# SCH_PCB-Hacker-Card-1_2024-07-07.net
KiCad netlist of a schematic drawn in EasyEDA
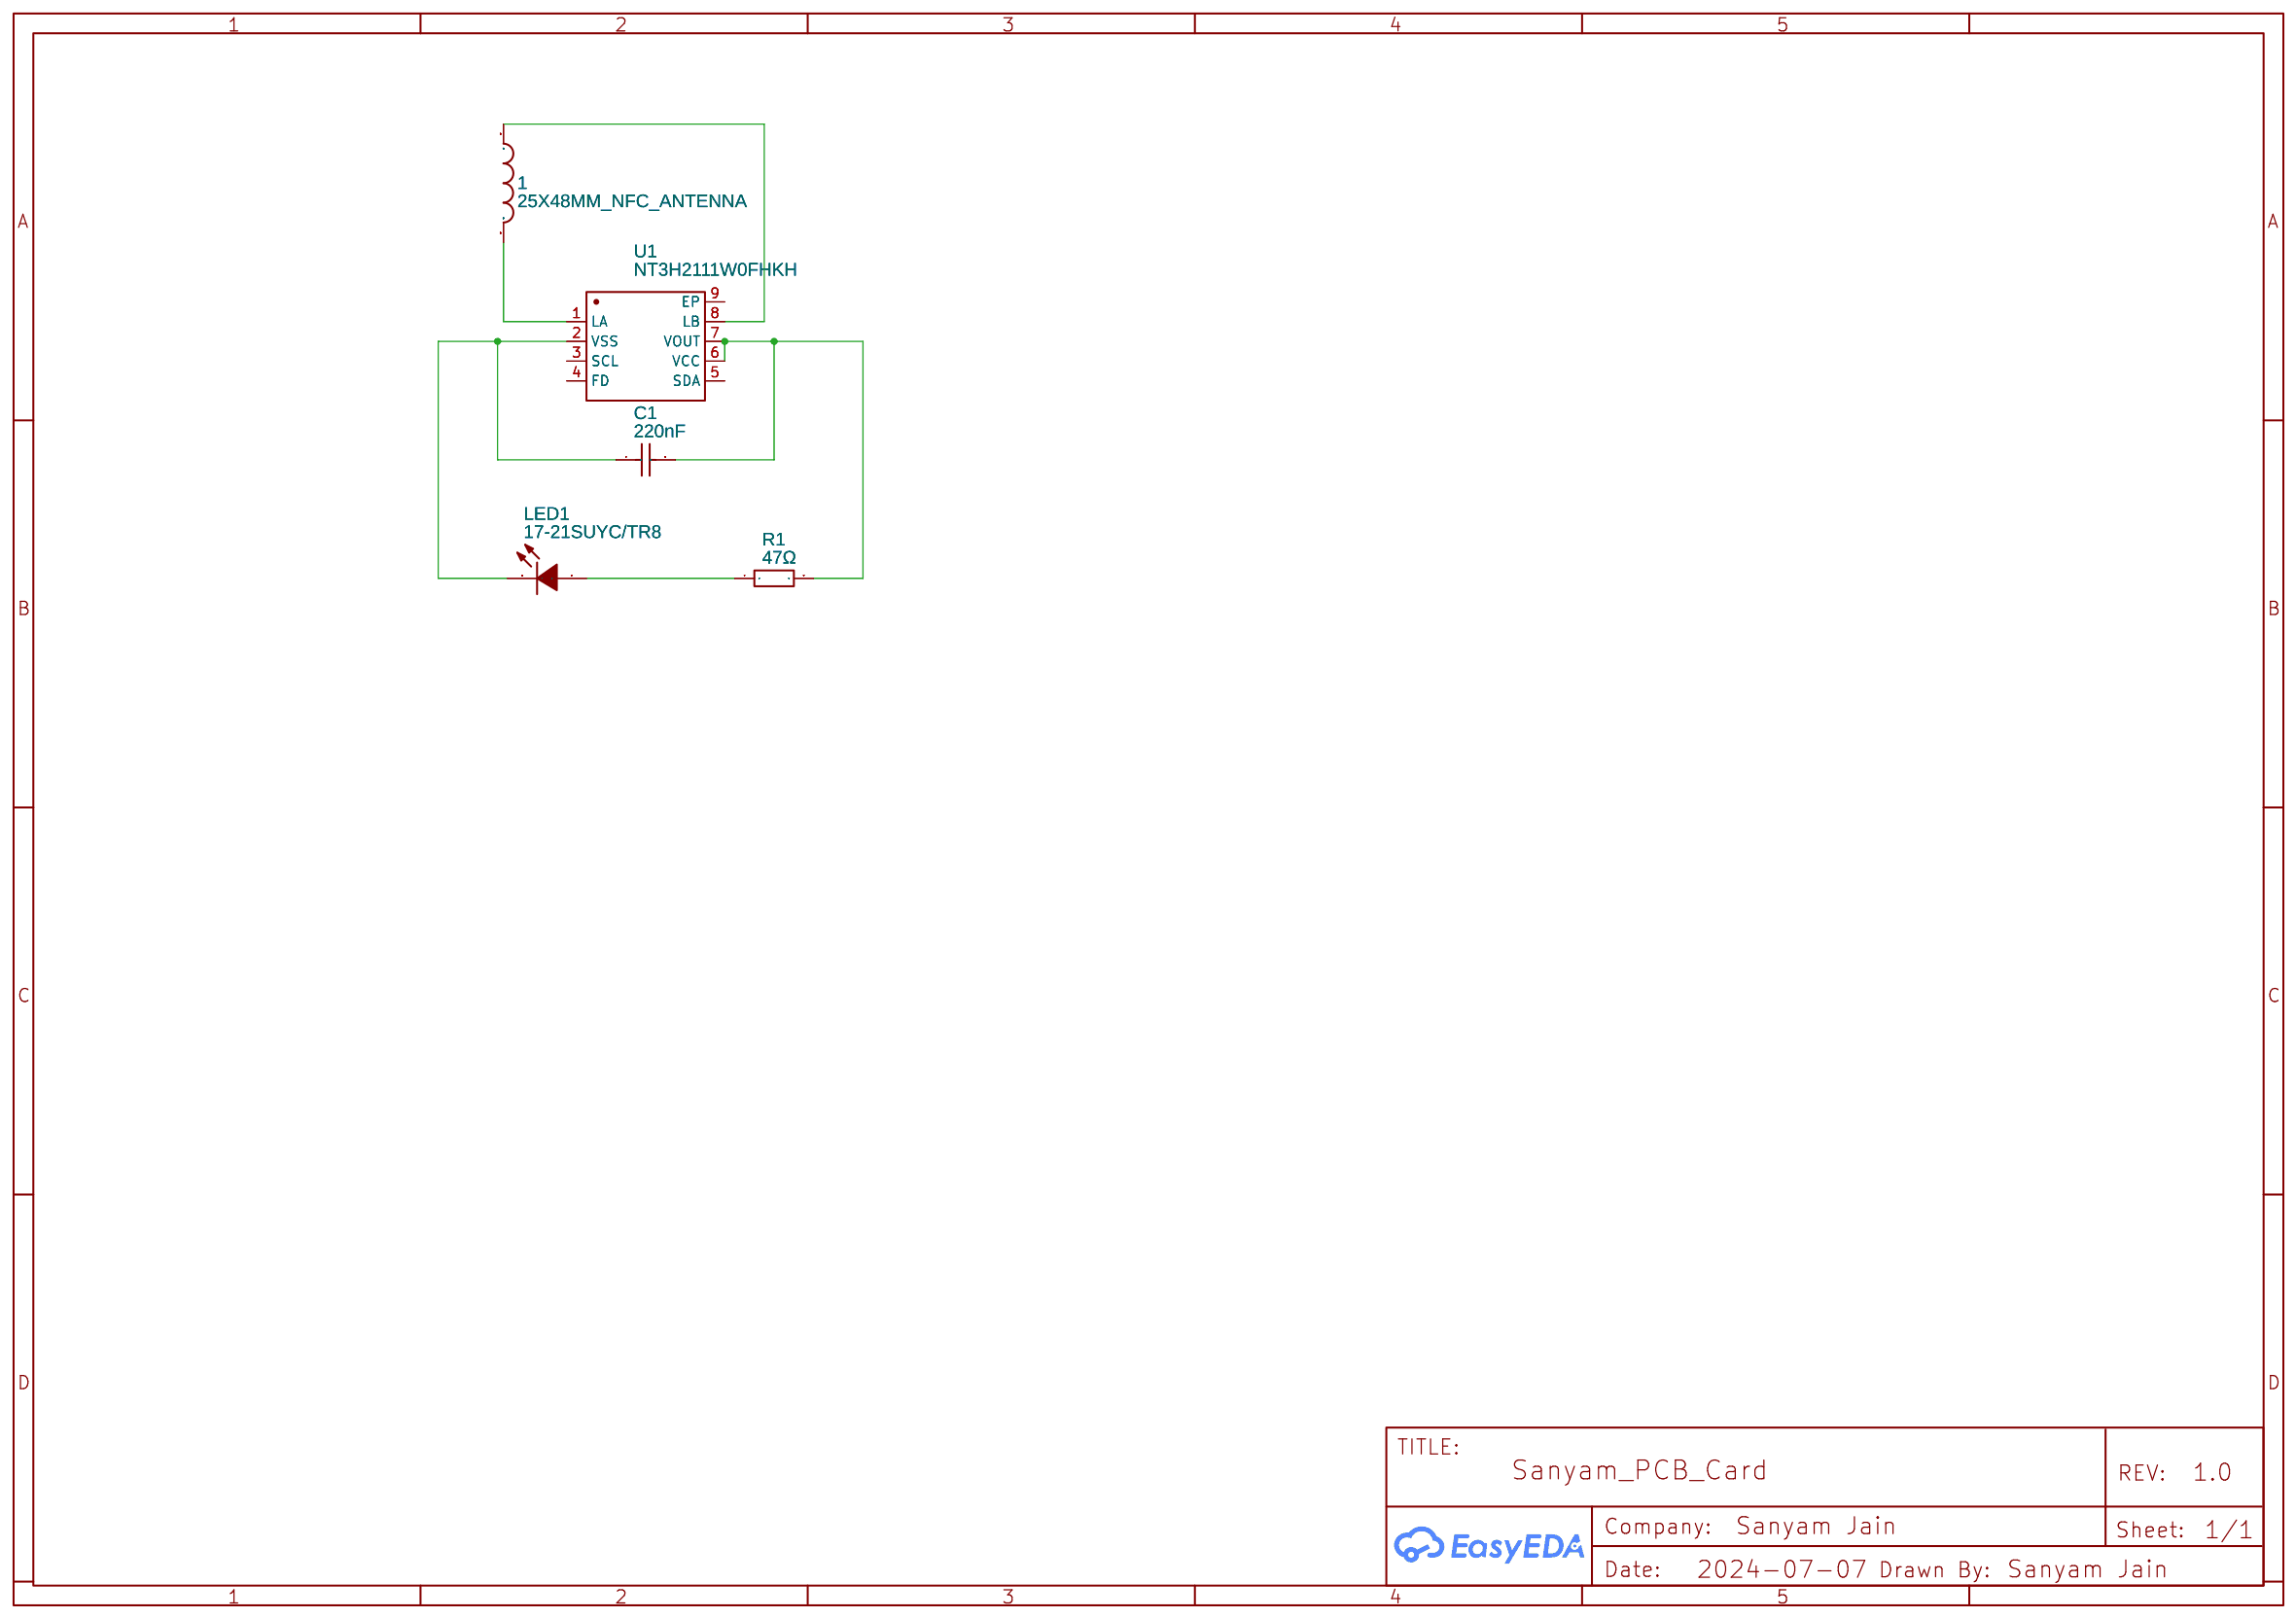
[diagram p0: schematic sheet]

(export (version "E")
  (design (tool "Eeschema 10.0.6"))
  (components
    (comp (ref "1") (value "25X48MM_NFC_ANTENNA") (libsource (lib "") (part "25X48MM_NFC_ANTENNA")))
    (comp (ref "C1")
      (value "220nF")
      (fields
        (field (name "Manufacturer Part") "CL10B224KA8NNNC")
        (field (name "Manufacturer") "SAMSUNG(三星)")
      )
      (libsource (lib "") (part "CL10B224KA8NNNC"))
    )
    (comp (ref "LED1")
      (value "17-21SUYC/TR8")
      (fields (field (name "Manufacturer Part") "KT-0805黄灯") (field (name "Manufacturer") "KENTO"))
      (libsource (lib "") (part "17-21SUYC/TR8"))
    )
    (comp (ref "R1")
      (value "47Ω")
      (fields
        (field (name "Manufacturer Part") "0603WAF470JT5E")
        (field (name "Manufacturer") "UNI-ROYAL(厚声)")
      )
      (libsource (lib "") (part "0603WAF470JT5E"))
    )
    (comp (ref "U1")
      (value "NT3H2111W0FHKH")
      (fields (field (name "Manufacturer") "NXP(恩智浦)"))
      (libsource (lib "") (part "NT3H2111W0FHKH"))
    )
  )
  (nets
    (net (code "1") (name "Net-(LED1-+)") (class "Default")
      (node (ref "LED1") (pin "1") (pinfunction "+_1") (pintype "unspecified"))
      (node (ref "R1") (pin "1") (pinfunction "1_1") (pintype "input"))
    )
    (net (code "2") (name "Net-(LED1--)") (class "Default")
      (node (ref "C1") (pin "1") (pinfunction "1_1") (pintype "input"))
      (node (ref "LED1") (pin "2") (pinfunction "-_2") (pintype "unspecified"))
      (node (ref "U1") (pin "2") (pinfunction "VSS_2") (pintype "unspecified"))
    )
    (net (code "3") (name "Net-(U1-LA)") (class "Default")
      (node (ref "1") (pin "P$2") (pinfunction "P$2_P$2") (pintype "bidirectional"))
      (node (ref "U1") (pin "1") (pinfunction "LA_1") (pintype "unspecified"))
    )
    (net (code "4") (name "Net-(U1-LB)") (class "Default")
      (node (ref "1") (pin "P$1") (pinfunction "P$1_P$1") (pintype "bidirectional"))
      (node (ref "U1") (pin "8") (pinfunction "LB_8") (pintype "unspecified"))
    )
    (net (code "5") (name "Net-(U1-VCC)") (class "Default")
      (node (ref "C1") (pin "2") (pinfunction "2_2") (pintype "input"))
      (node (ref "R1") (pin "2") (pinfunction "2_2") (pintype "input"))
      (node (ref "U1") (pin "6") (pinfunction "VCC_6") (pintype "unspecified"))
      (node (ref "U1") (pin "7") (pinfunction "VOUT_7") (pintype "unspecified"))
    )
    (net (code "6") (name "unconnected-(U1-EP-Pad9)") (class "Default")
      (node (ref "U1") (pin "9") (pinfunction "EP_9") (pintype "unspecified"))
    )
    (net (code "7") (name "unconnected-(U1-FD-Pad4)") (class "Default")
      (node (ref "U1") (pin "4") (pinfunction "FD_4") (pintype "unspecified"))
    )
    (net (code "8") (name "unconnected-(U1-SCL-Pad3)") (class "Default")
      (node (ref "U1") (pin "3") (pinfunction "SCL_3") (pintype "unspecified"))
    )
    (net (code "9") (name "unconnected-(U1-SDA-Pad5)") (class "Default")
      (node (ref "U1") (pin "5") (pinfunction "SDA_5") (pintype "unspecified"))
    )
  )
)
